# F0-lamp.net
KiCad netlist of a schematic drawn in EAGLE
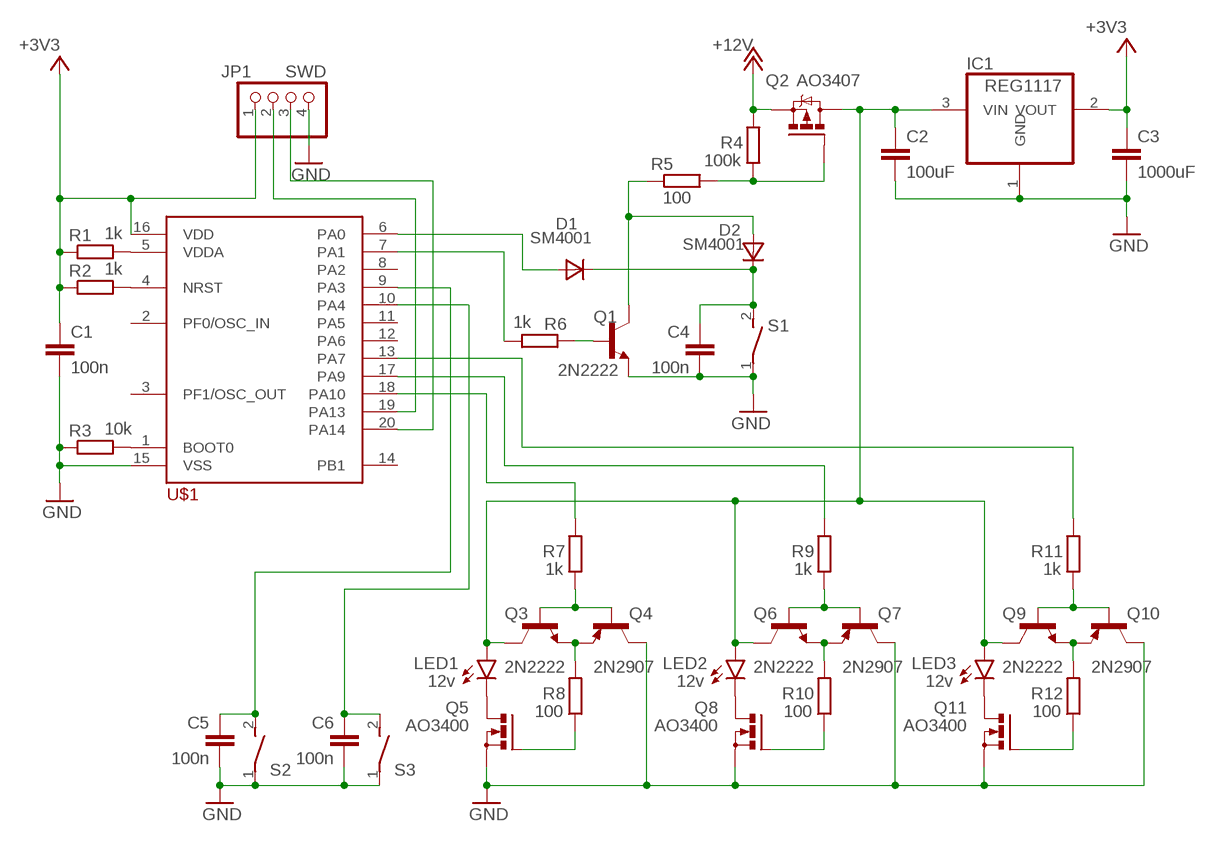
[diagram p0: schematic, sheet 1]

(export (version "E")
  (design (tool "Eeschema 10.0.6"))
  (components
    (comp (ref "C1")
      (value "100n")
      (footprint "eagle-import:C0805")
      (libsource (lib "eagle-import") (part "C-EUC0805"))
    )
    (comp (ref "C2")
      (value "100uF")
      (footprint "eagle-import:C0805")
      (libsource (lib "eagle-import") (part "C-EUC0805"))
    )
    (comp (ref "C3")
      (value "1000uF")
      (footprint "eagle-import:C0805")
      (libsource (lib "eagle-import") (part "C-EUC0805"))
    )
    (comp (ref "C4")
      (value "100n")
      (footprint "eagle-import:C0805")
      (libsource (lib "eagle-import") (part "C-EUC0805"))
    )
    (comp (ref "C5")
      (value "100n")
      (footprint "eagle-import:C0805")
      (libsource (lib "eagle-import") (part "C-EUC0805"))
    )
    (comp (ref "C6")
      (value "100n")
      (footprint "eagle-import:C0805")
      (libsource (lib "eagle-import") (part "C-EUC0805"))
    )
    (comp (ref "D1")
      (value "SM4001")
      (footprint "eagle-import:MELF-MLL41")
      (libsource (lib "eagle-import") (part "SM4001"))
    )
    (comp (ref "D2")
      (value "SM4001")
      (footprint "eagle-import:MELF-MLL41")
      (libsource (lib "eagle-import") (part "SM4001"))
    )
    (comp (ref "IC1")
      (value "REG1117")
      (footprint "eagle-import:SOT223")
      (libsource (lib "eagle-import") (part "REG1117"))
    )
    (comp (ref "JP1")
      (value "SWD")
      (footprint "eagle-import:1X04")
      (libsource (lib "eagle-import") (part "PINHD-1X4"))
    )
    (comp (ref "LED1")
      (value "12v")
      (footprint "eagle-import:LUMILED+")
      (libsource (lib "eagle-import") (part "LED-LUMILED+"))
    )
    (comp (ref "LED2")
      (value "12v")
      (footprint "eagle-import:LUMILED+")
      (libsource (lib "eagle-import") (part "LED-LUMILED+"))
    )
    (comp (ref "LED3")
      (value "12v")
      (footprint "eagle-import:LUMILED+")
      (libsource (lib "eagle-import") (part "LED-LUMILED+"))
    )
    (comp (ref "Q1")
      (value "2N2222")
      (footprint "eagle-import:TO18")
      (libsource (lib "eagle-import") (part "2N2222"))
    )
    (comp (ref "Q2")
      (value "AO3407")
      (footprint "eagle-import:TO220BH")
      (libsource (lib "eagle-import") (part "IRF4905"))
    )
    (comp (ref "Q3")
      (value "2N2222")
      (footprint "eagle-import:TO18")
      (libsource (lib "eagle-import") (part "2N2222"))
    )
    (comp (ref "Q4")
      (value "2N2907")
      (footprint "eagle-import:TO18")
      (libsource (lib "eagle-import") (part "2N2907"))
    )
    (comp (ref "Q5")
      (value "AO3400")
      (footprint "eagle-import:TO220BV")
      (libsource (lib "eagle-import") (part "PMOSFET_NTO220BV"))
    )
    (comp (ref "Q6")
      (value "2N2222")
      (footprint "eagle-import:TO18")
      (libsource (lib "eagle-import") (part "2N2222"))
    )
    (comp (ref "Q7")
      (value "2N2907")
      (footprint "eagle-import:TO18")
      (libsource (lib "eagle-import") (part "2N2907"))
    )
    (comp (ref "Q8")
      (value "AO3400")
      (footprint "eagle-import:TO220BV")
      (libsource (lib "eagle-import") (part "PMOSFET_NTO220BV"))
    )
    (comp (ref "Q9")
      (value "2N2222")
      (footprint "eagle-import:TO18")
      (libsource (lib "eagle-import") (part "2N2222"))
    )
    (comp (ref "Q10")
      (value "2N2907")
      (footprint "eagle-import:TO18")
      (libsource (lib "eagle-import") (part "2N2907"))
    )
    (comp (ref "Q11")
      (value "AO3400")
      (footprint "eagle-import:TO220BV")
      (libsource (lib "eagle-import") (part "PMOSFET_NTO220BV"))
    )
    (comp (ref "R1")
      (value "1k")
      (footprint "eagle-import:1812X7R")
      (libsource (lib "eagle-import") (part "R-EU_1812X7R"))
    )
    (comp (ref "R2")
      (value "1k")
      (footprint "eagle-import:1812X7R")
      (libsource (lib "eagle-import") (part "R-EU_1812X7R"))
    )
    (comp (ref "R3")
      (value "10k")
      (footprint "eagle-import:1812X7R")
      (libsource (lib "eagle-import") (part "R-EU_1812X7R"))
    )
    (comp (ref "R4")
      (value "100k")
      (footprint "eagle-import:1812X7R")
      (libsource (lib "eagle-import") (part "R-EU_1812X7R"))
    )
    (comp (ref "R5")
      (value "100")
      (footprint "eagle-import:1812X7R")
      (libsource (lib "eagle-import") (part "R-EU_1812X7R"))
    )
    (comp (ref "R6")
      (value "1k")
      (footprint "eagle-import:1812X7R")
      (libsource (lib "eagle-import") (part "R-EU_1812X7R"))
    )
    (comp (ref "R7")
      (value "1k")
      (footprint "eagle-import:1812X7R")
      (libsource (lib "eagle-import") (part "R-EU_1812X7R"))
    )
    (comp (ref "R8")
      (value "100")
      (footprint "eagle-import:1812X7R")
      (libsource (lib "eagle-import") (part "R-EU_1812X7R"))
    )
    (comp (ref "R9")
      (value "1k")
      (footprint "eagle-import:1812X7R")
      (libsource (lib "eagle-import") (part "R-EU_1812X7R"))
    )
    (comp (ref "R10")
      (value "100")
      (footprint "eagle-import:1812X7R")
      (libsource (lib "eagle-import") (part "R-EU_1812X7R"))
    )
    (comp (ref "R11")
      (value "1k")
      (footprint "eagle-import:1812X7R")
      (libsource (lib "eagle-import") (part "R-EU_1812X7R"))
    )
    (comp (ref "R12")
      (value "100")
      (footprint "eagle-import:1812X7R")
      (libsource (lib "eagle-import") (part "R-EU_1812X7R"))
    )
    (comp (ref "S1")
      (value "Button")
      (footprint "eagle-import:SWITCH_01")
      (libsource (lib "eagle-import") (part "SWITCH_01"))
    )
    (comp (ref "S2")
      (value "Button")
      (footprint "eagle-import:SWITCH_01")
      (libsource (lib "eagle-import") (part "SWITCH_01"))
    )
    (comp (ref "S3")
      (value "Button")
      (footprint "eagle-import:SWITCH_01")
      (libsource (lib "eagle-import") (part "SWITCH_01"))
    )
    (comp (ref "U$1")
      (value "STM32F030F4")
      (footprint "eagle-import:TSSOP20")
      (libsource (lib "eagle-import") (part "STM32F030F4"))
    )
  )
  (nets
    (net (code "1") (name "+3V3") (class "Default")
      (node (ref "C1") (pin "1") (pinfunction "1_1") (pintype "passive"))
      (node (ref "C3") (pin "1") (pinfunction "1_1") (pintype "passive"))
      (node (ref "IC1") (pin "2") (pinfunction "VOUT_2") (pintype "output"))
      (node (ref "JP1") (pin "1") (pinfunction "1_1") (pintype "passive"))
      (node (ref "R1") (pin "1") (pinfunction "1_1") (pintype "passive"))
      (node (ref "R2") (pin "1") (pinfunction "1_1") (pintype "passive"))
      (node (ref "U$1") (pin "16") (pinfunction "VDD_16") (pintype "bidirectional"))
    )
    (net (code "2") (name "+12V") (class "Default")
      (node (ref "Q2") (pin "S") (pinfunction "S_S") (pintype "passive"))
      (node (ref "R4") (pin "2") (pinfunction "2_2") (pintype "passive"))
    )
    (net (code "3") (name "GND") (class "Default")
      (node (ref "C1") (pin "2") (pinfunction "2_2") (pintype "passive"))
      (node (ref "C2") (pin "2") (pinfunction "2_2") (pintype "passive"))
      (node (ref "C3") (pin "2") (pinfunction "2_2") (pintype "passive"))
      (node (ref "C4") (pin "2") (pinfunction "2_2") (pintype "passive"))
      (node (ref "C5") (pin "2") (pinfunction "2_2") (pintype "passive"))
      (node (ref "C6") (pin "2") (pinfunction "2_2") (pintype "passive"))
      (node (ref "IC1") (pin "1") (pinfunction "GND_1") (pintype "power_in"))
      (node (ref "JP1") (pin "4") (pinfunction "4_4") (pintype "passive"))
      (node (ref "Q1") (pin "1") (pinfunction "E_1") (pintype "passive"))
      (node (ref "Q10") (pin "3") (pinfunction "C_3") (pintype "passive"))
      (node (ref "Q11") (pin "S") (pinfunction "S_S") (pintype "passive"))
      (node (ref "Q4") (pin "3") (pinfunction "C_3") (pintype "passive"))
      (node (ref "Q5") (pin "S") (pinfunction "S_S") (pintype "passive"))
      (node (ref "Q7") (pin "3") (pinfunction "C_3") (pintype "passive"))
      (node (ref "Q8") (pin "S") (pinfunction "S_S") (pintype "passive"))
      (node (ref "R3") (pin "1") (pinfunction "1_1") (pintype "passive"))
      (node (ref "S1") (pin "1") (pinfunction "1_1") (pintype "passive"))
      (node (ref "S2") (pin "1") (pinfunction "1_1") (pintype "passive"))
      (node (ref "S3") (pin "1") (pinfunction "1_1") (pintype "passive"))
      (node (ref "U$1") (pin "15") (pinfunction "VSS_15") (pintype "bidirectional"))
    )
    (net (code "4") (name "Net-(C4-Pad1)") (class "Default")
      (node (ref "C4") (pin "1") (pinfunction "1_1") (pintype "passive"))
      (node (ref "D1") (pin "C") (pinfunction "C_C") (pintype "passive"))
      (node (ref "D2") (pin "C") (pinfunction "C_C") (pintype "passive"))
      (node (ref "S1") (pin "2") (pinfunction "2_2") (pintype "passive"))
    )
    (net (code "5") (name "Net-(IC1-VIN)") (class "Default")
      (node (ref "C2") (pin "1") (pinfunction "1_1") (pintype "passive"))
      (node (ref "IC1") (pin "3") (pinfunction "VIN_3") (pintype "input"))
      (node (ref "LED1") (pin "2+") (pinfunction "A_2+") (pintype "passive"))
      (node (ref "LED2") (pin "2+") (pinfunction "A_2+") (pintype "passive"))
      (node (ref "LED3") (pin "2+") (pinfunction "A_2+") (pintype "passive"))
      (node (ref "Q2") (pin "D") (pinfunction "D_D") (pintype "passive"))
      (node (ref "Q3") (pin "3") (pinfunction "C_3") (pintype "passive"))
      (node (ref "Q6") (pin "3") (pinfunction "C_3") (pintype "passive"))
      (node (ref "Q9") (pin "3") (pinfunction "C_3") (pintype "passive"))
    )
    (net (code "6") (name "Net-(LED1-C)") (class "Default")
      (node (ref "LED1") (pin "4-") (pinfunction "C_4-") (pintype "passive"))
      (node (ref "Q5") (pin "D") (pinfunction "D_D") (pintype "passive"))
    )
    (net (code "7") (name "Net-(LED2-C)") (class "Default")
      (node (ref "LED2") (pin "4-") (pinfunction "C_4-") (pintype "passive"))
      (node (ref "Q8") (pin "D") (pinfunction "D_D") (pintype "passive"))
    )
    (net (code "8") (name "Net-(LED3-C)") (class "Default")
      (node (ref "LED3") (pin "4-") (pinfunction "C_4-") (pintype "passive"))
      (node (ref "Q11") (pin "D") (pinfunction "D_D") (pintype "passive"))
    )
    (net (code "9") (name "Net-(Q1-B)") (class "Default")
      (node (ref "Q1") (pin "2") (pinfunction "B_2") (pintype "passive"))
      (node (ref "R6") (pin "1") (pinfunction "1_1") (pintype "passive"))
    )
    (net (code "10") (name "Net-(Q1-C)") (class "Default")
      (node (ref "D2") (pin "A") (pinfunction "A_A") (pintype "passive"))
      (node (ref "Q1") (pin "3") (pinfunction "C_3") (pintype "passive"))
      (node (ref "R5") (pin "2") (pinfunction "2_2") (pintype "passive"))
    )
    (net (code "11") (name "Net-(Q2-PadG)") (class "Default")
      (node (ref "Q2") (pin "G") (pinfunction "G_G") (pintype "passive"))
      (node (ref "R4") (pin "1") (pinfunction "1_1") (pintype "passive"))
      (node (ref "R5") (pin "1") (pinfunction "1_1") (pintype "passive"))
    )
    (net (code "12") (name "Net-(Q3-B)") (class "Default")
      (node (ref "Q3") (pin "2") (pinfunction "B_2") (pintype "passive"))
      (node (ref "Q4") (pin "2") (pinfunction "B_2") (pintype "passive"))
      (node (ref "R7") (pin "1") (pinfunction "1_1") (pintype "passive"))
    )
    (net (code "13") (name "Net-(Q3-E)") (class "Default")
      (node (ref "Q3") (pin "1") (pinfunction "E_1") (pintype "passive"))
      (node (ref "Q4") (pin "1") (pinfunction "E_1") (pintype "passive"))
      (node (ref "R8") (pin "2") (pinfunction "2_2") (pintype "passive"))
    )
    (net (code "14") (name "Net-(Q5-PadG)") (class "Default")
      (node (ref "Q5") (pin "G") (pinfunction "G_G") (pintype "passive"))
      (node (ref "R8") (pin "1") (pinfunction "1_1") (pintype "passive"))
    )
    (net (code "15") (name "Net-(Q6-B)") (class "Default")
      (node (ref "Q6") (pin "2") (pinfunction "B_2") (pintype "passive"))
      (node (ref "Q7") (pin "2") (pinfunction "B_2") (pintype "passive"))
      (node (ref "R9") (pin "1") (pinfunction "1_1") (pintype "passive"))
    )
    (net (code "16") (name "Net-(Q6-E)") (class "Default")
      (node (ref "Q6") (pin "1") (pinfunction "E_1") (pintype "passive"))
      (node (ref "Q7") (pin "1") (pinfunction "E_1") (pintype "passive"))
      (node (ref "R10") (pin "2") (pinfunction "2_2") (pintype "passive"))
    )
    (net (code "17") (name "Net-(Q8-PadG)") (class "Default")
      (node (ref "Q8") (pin "G") (pinfunction "G_G") (pintype "passive"))
      (node (ref "R10") (pin "1") (pinfunction "1_1") (pintype "passive"))
    )
    (net (code "18") (name "Net-(Q10-B)") (class "Default")
      (node (ref "Q10") (pin "2") (pinfunction "B_2") (pintype "passive"))
      (node (ref "Q9") (pin "2") (pinfunction "B_2") (pintype "passive"))
      (node (ref "R11") (pin "1") (pinfunction "1_1") (pintype "passive"))
    )
    (net (code "19") (name "Net-(Q10-E)") (class "Default")
      (node (ref "Q10") (pin "1") (pinfunction "E_1") (pintype "passive"))
      (node (ref "Q9") (pin "1") (pinfunction "E_1") (pintype "passive"))
      (node (ref "R12") (pin "2") (pinfunction "2_2") (pintype "passive"))
    )
    (net (code "20") (name "Net-(Q11-PadG)") (class "Default")
      (node (ref "Q11") (pin "G") (pinfunction "G_G") (pintype "passive"))
      (node (ref "R12") (pin "1") (pinfunction "1_1") (pintype "passive"))
    )
    (net (code "21") (name "Net-(U$1-BOOT0)") (class "Default")
      (node (ref "R3") (pin "2") (pinfunction "2_2") (pintype "passive"))
      (node (ref "U$1") (pin "1") (pinfunction "BOOT0_1") (pintype "bidirectional"))
    )
    (net (code "22") (name "Net-(U$1-NRST)") (class "Default")
      (node (ref "R2") (pin "2") (pinfunction "2_2") (pintype "passive"))
      (node (ref "U$1") (pin "4") (pinfunction "NRST_4") (pintype "bidirectional"))
    )
    (net (code "23") (name "Net-(U$1-PA0)") (class "Default")
      (node (ref "D1") (pin "A") (pinfunction "A_A") (pintype "passive"))
      (node (ref "U$1") (pin "6") (pinfunction "PA0_6") (pintype "bidirectional"))
    )
    (net (code "24") (name "Net-(U$1-PA1)") (class "Default")
      (node (ref "R6") (pin "2") (pinfunction "2_2") (pintype "passive"))
      (node (ref "U$1") (pin "7") (pinfunction "PA1_7") (pintype "bidirectional"))
    )
    (net (code "25") (name "Net-(U$1-PA3)") (class "Default")
      (node (ref "C5") (pin "1") (pinfunction "1_1") (pintype "passive"))
      (node (ref "S2") (pin "2") (pinfunction "2_2") (pintype "passive"))
      (node (ref "U$1") (pin "9") (pinfunction "PA3_9") (pintype "bidirectional"))
    )
    (net (code "26") (name "Net-(U$1-PA4)") (class "Default")
      (node (ref "C6") (pin "1") (pinfunction "1_1") (pintype "passive"))
      (node (ref "S3") (pin "2") (pinfunction "2_2") (pintype "passive"))
      (node (ref "U$1") (pin "10") (pinfunction "PA4_10") (pintype "bidirectional"))
    )
    (net (code "27") (name "Net-(U$1-PA7)") (class "Default")
      (node (ref "R11") (pin "2") (pinfunction "2_2") (pintype "passive"))
      (node (ref "U$1") (pin "13") (pinfunction "PA7_13") (pintype "bidirectional"))
    )
    (net (code "28") (name "Net-(U$1-PA9)") (class "Default")
      (node (ref "R9") (pin "2") (pinfunction "2_2") (pintype "passive"))
      (node (ref "U$1") (pin "17") (pinfunction "PA9_17") (pintype "bidirectional"))
    )
    (net (code "29") (name "Net-(U$1-PA10)") (class "Default")
      (node (ref "R7") (pin "2") (pinfunction "2_2") (pintype "passive"))
      (node (ref "U$1") (pin "18") (pinfunction "PA10_18") (pintype "bidirectional"))
    )
    (net (code "30") (name "Net-(U$1-PA13)") (class "Default")
      (node (ref "JP1") (pin "2") (pinfunction "2_2") (pintype "passive"))
      (node (ref "U$1") (pin "19") (pinfunction "PA13_19") (pintype "bidirectional"))
    )
    (net (code "31") (name "Net-(U$1-PA14)") (class "Default")
      (node (ref "JP1") (pin "3") (pinfunction "3_3") (pintype "passive"))
      (node (ref "U$1") (pin "20") (pinfunction "PA14_20") (pintype "bidirectional"))
    )
    (net (code "32") (name "Net-(U$1-VDDA)") (class "Default")
      (node (ref "R1") (pin "2") (pinfunction "2_2") (pintype "passive"))
      (node (ref "U$1") (pin "5") (pinfunction "VDDA_5") (pintype "bidirectional"))
    )
    (net (code "33") (name "unconnected-(U$1-PA2-Pad8)") (class "Default")
      (node (ref "U$1") (pin "8") (pinfunction "PA2_8") (pintype "bidirectional"))
    )
    (net (code "34") (name "unconnected-(U$1-PA5-Pad11)") (class "Default")
      (node (ref "U$1") (pin "11") (pinfunction "PA5_11") (pintype "bidirectional"))
    )
    (net (code "35") (name "unconnected-(U$1-PA6-Pad12)") (class "Default")
      (node (ref "U$1") (pin "12") (pinfunction "PA6_12") (pintype "bidirectional"))
    )
    (net (code "36") (name "unconnected-(U$1-PB1-Pad14)") (class "Default")
      (node (ref "U$1") (pin "14") (pinfunction "PB1_14") (pintype "bidirectional"))
    )
    (net (code "37") (name "unconnected-(U$1-PF0{slash}OSC_IN-Pad2)") (class "Default")
      (node (ref "U$1") (pin "2") (pinfunction "PF0/OSC_IN_2") (pintype "bidirectional"))
    )
    (net (code "38") (name "unconnected-(U$1-PF1{slash}OSC_OUT-Pad3)") (class "Default")
      (node (ref "U$1") (pin "3") (pinfunction "PF1/OSC_OUT_3") (pintype "bidirectional"))
    )
  )
)
